# SGP30_Breakout.net
KiCad netlist of a schematic drawn in EAGLE
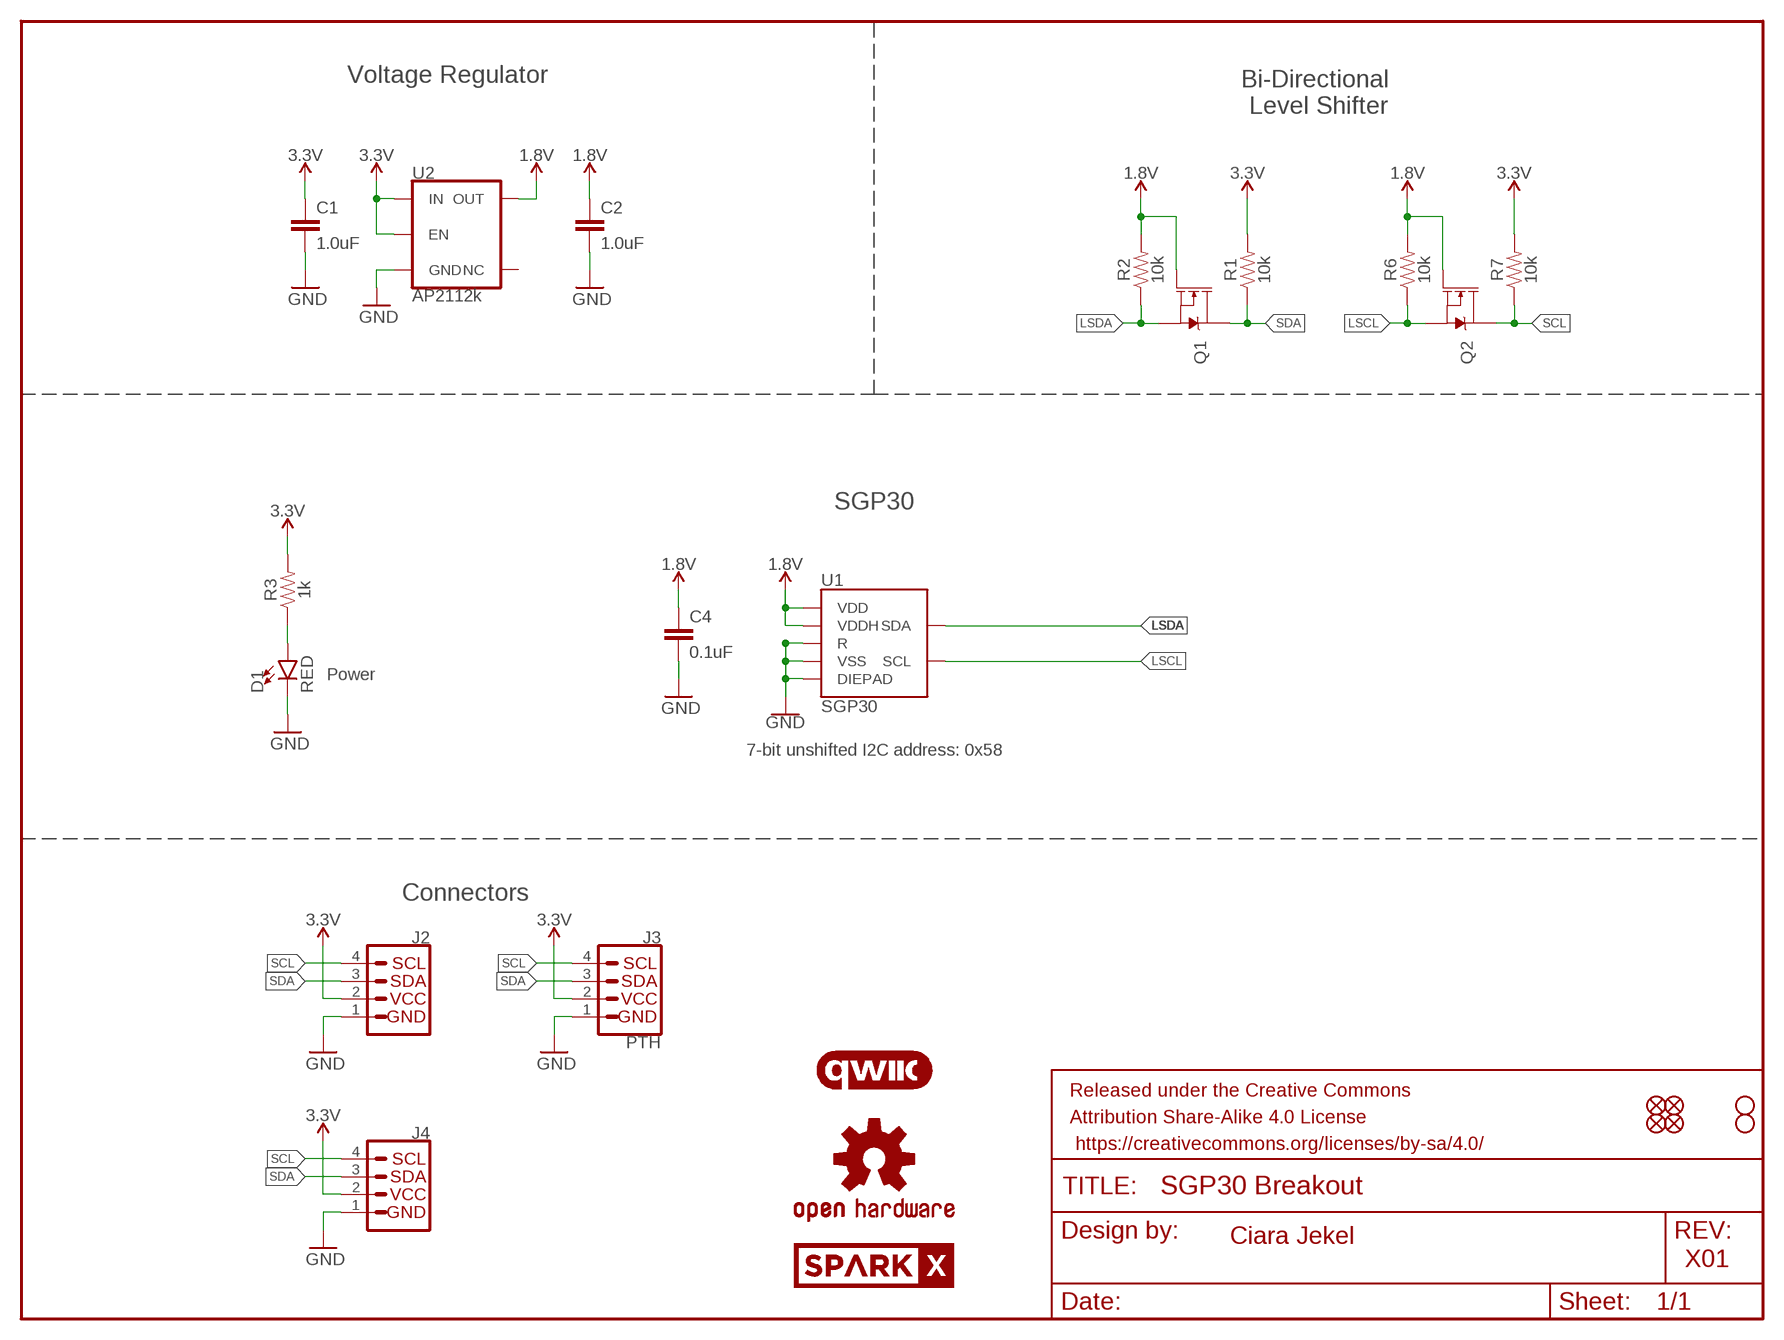
[diagram p0: schematic, sheet 1]

(export (version "E")
  (design (tool "Eeschema 10.0.6"))
  (components
    (comp (ref "C1")
      (value "1.0uF")
      (footprint "eagle-import:0603")
      (libsource (lib "eagle-import") (part "1.0UF-0603-16V-10%"))
    )
    (comp (ref "C2")
      (value "1.0uF")
      (footprint "eagle-import:0603")
      (libsource (lib "eagle-import") (part "1.0UF-0603-16V-10%"))
    )
    (comp (ref "C4")
      (value "0.1uF")
      (footprint "eagle-import:0603")
      (libsource (lib "eagle-import") (part "0.1UF-0603-25V-(+80/-20%)"))
    )
    (comp (ref "D1")
      (value "RED")
      (footprint "eagle-import:LED-0603")
      (libsource (lib "eagle-import") (part "LED-RED0603"))
    )
    (comp (ref "FRAME1")
      (value "FRAME-LETTER")
      (footprint "eagle-import:CREATIVE_COMMONS")
      (libsource (lib "eagle-import") (part "FRAME-LETTER"))
    )
    (comp (ref "J2")
      (value "QWIIC_CONNECTORJS-1MM")
      (footprint "eagle-import:1X04_1MM_RA")
      (libsource (lib "eagle-import") (part "QWIIC_CONNECTORJS-1MM"))
    )
    (comp (ref "J3")
      (value "PTH")
      (footprint "eagle-import:1X04_NO_SILK")
      (libsource (lib "eagle-import") (part "I2C_STANDARD_NO_SILK"))
    )
    (comp (ref "J4")
      (value "QWIIC_CONNECTORJS-1MM")
      (footprint "eagle-import:1X04_1MM_RA")
      (libsource (lib "eagle-import") (part "QWIIC_CONNECTORJS-1MM"))
    )
    (comp (ref "JP1")
      (value "FIDUCIALUFIDUCIAL")
      (footprint "eagle-import:MICRO-FIDUCIAL")
      (libsource (lib "eagle-import") (part "FIDUCIALUFIDUCIAL"))
    )
    (comp (ref "JP2")
      (value "FIDUCIALUFIDUCIAL")
      (footprint "eagle-import:MICRO-FIDUCIAL")
      (libsource (lib "eagle-import") (part "FIDUCIALUFIDUCIAL"))
    )
    (comp (ref "JP3")
      (value "STAND-OFF")
      (footprint "eagle-import:STAND-OFF")
      (libsource (lib "eagle-import") (part "STAND-OFF"))
    )
    (comp (ref "JP4")
      (value "STAND-OFF")
      (footprint "eagle-import:STAND-OFF")
      (libsource (lib "eagle-import") (part "STAND-OFF"))
    )
    (comp (ref "JP5")
      (value "FIDUCIALUFIDUCIAL")
      (footprint "eagle-import:MICRO-FIDUCIAL")
      (libsource (lib "eagle-import") (part "FIDUCIALUFIDUCIAL"))
    )
    (comp (ref "JP6")
      (value "FIDUCIALUFIDUCIAL")
      (footprint "eagle-import:MICRO-FIDUCIAL")
      (libsource (lib "eagle-import") (part "FIDUCIALUFIDUCIAL"))
    )
    (comp (ref "LOGO1")
      (value "OSHW-LOGOMINI")
      (footprint "eagle-import:OSHW-LOGO-MINI")
      (libsource (lib "eagle-import") (part "OSHW-LOGOMINI"))
    )
    (comp (ref "Q1")
      (value "MOSFET-NCH-BSS138")
      (footprint "eagle-import:SOT23-3")
      (libsource (lib "eagle-import") (part "MOSFET-NCH-BSS138"))
    )
    (comp (ref "Q2")
      (value "MOSFET-NCH-BSS138")
      (footprint "eagle-import:SOT23-3")
      (libsource (lib "eagle-import") (part "MOSFET-NCH-BSS138"))
    )
    (comp (ref "R1")
      (value "10k")
      (footprint "eagle-import:0603")
      (libsource (lib "eagle-import") (part "10KOHM-0603-1/10W-1%"))
    )
    (comp (ref "R2")
      (value "10k")
      (footprint "eagle-import:0603")
      (libsource (lib "eagle-import") (part "10KOHM-0603-1/10W-1%"))
    )
    (comp (ref "R3")
      (value "1k")
      (footprint "eagle-import:0603")
      (libsource (lib "eagle-import") (part "1KOHM-0603-1/10W-1%"))
    )
    (comp (ref "R6")
      (value "10k")
      (footprint "eagle-import:0603")
      (libsource (lib "eagle-import") (part "10KOHM-0603-1/10W-1%"))
    )
    (comp (ref "R7")
      (value "10k")
      (footprint "eagle-import:0603")
      (libsource (lib "eagle-import") (part "10KOHM-0603-1/10W-1%"))
    )
    (comp (ref "U$1")
      (value "SPARKX-LOGO4")
      (footprint "eagle-import:SPARKX-MEDIUM")
      (libsource (lib "eagle-import") (part "SPARKX-LOGO4"))
    )
    (comp (ref "U$2")
      (value "SPARKX-LOGO4")
      (footprint "eagle-import:SPARKX-MEDIUM")
      (libsource (lib "eagle-import") (part "SPARKX-LOGO4"))
    )
    (comp (ref "U$9")
      (value "QWIIC_LOGO_7MM")
      (footprint "eagle-import:QWIIC_7MM")
      (libsource (lib "eagle-import") (part "QWIIC_LOGO_7MM"))
    )
    (comp (ref "U1")
      (value "SGP30")
      (footprint "eagle-import:SGP30")
      (libsource (lib "eagle-import") (part "SGP30"))
    )
    (comp (ref "U2")
      (value "AP2112k")
      (footprint "eagle-import:SOT23-5")
      (libsource (lib "eagle-import") (part "MIC5504"))
    )
  )
  (nets
    (net (code "1") (name "1.8V") (class "Default")
      (node (ref "C2") (pin "1") (pinfunction "1_1") (pintype "passive"))
      (node (ref "C4") (pin "1") (pinfunction "1_1") (pintype "passive"))
      (node (ref "Q1") (pin "1") (pinfunction "G_1") (pintype "bidirectional"))
      (node (ref "Q2") (pin "1") (pinfunction "G_1") (pintype "bidirectional"))
      (node (ref "R2") (pin "2") (pinfunction "2_2") (pintype "passive"))
      (node (ref "R6") (pin "2") (pinfunction "2_2") (pintype "passive"))
      (node (ref "U1") (pin "1") (pinfunction "VDD_1") (pintype "bidirectional"))
      (node (ref "U1") (pin "5") (pinfunction "VDDH_5") (pintype "bidirectional"))
      (node (ref "U2") (pin "5") (pinfunction "OUT_5") (pintype "passive"))
    )
    (net (code "2") (name "3.3V") (class "Default")
      (node (ref "C1") (pin "1") (pinfunction "1_1") (pintype "passive"))
      (node (ref "J2") (pin "2") (pinfunction "2_2") (pintype "power_in"))
      (node (ref "J3") (pin "2") (pinfunction "VCC_2") (pintype "power_in"))
      (node (ref "J4") (pin "2") (pinfunction "2_2") (pintype "power_in"))
      (node (ref "R1") (pin "2") (pinfunction "2_2") (pintype "passive"))
      (node (ref "R3") (pin "2") (pinfunction "2_2") (pintype "passive"))
      (node (ref "R7") (pin "2") (pinfunction "2_2") (pintype "passive"))
      (node (ref "U2") (pin "1") (pinfunction "IN_1") (pintype "input"))
      (node (ref "U2") (pin "3") (pinfunction "EN_3") (pintype "input"))
    )
    (net (code "3") (name "GND") (class "Default")
      (node (ref "C1") (pin "2") (pinfunction "2_2") (pintype "passive"))
      (node (ref "C2") (pin "2") (pinfunction "2_2") (pintype "passive"))
      (node (ref "C4") (pin "2") (pinfunction "2_2") (pintype "passive"))
      (node (ref "D1") (pin "C") (pinfunction "C_C") (pintype "passive"))
      (node (ref "J2") (pin "1") (pinfunction "1_1") (pintype "power_in"))
      (node (ref "J3") (pin "1") (pinfunction "GND_1") (pintype "power_in"))
      (node (ref "J4") (pin "1") (pinfunction "1_1") (pintype "power_in"))
      (node (ref "U1") (pin "2") (pinfunction "VSS_2") (pintype "bidirectional"))
      (node (ref "U1") (pin "4") (pinfunction "R_4") (pintype "bidirectional"))
      (node (ref "U1") (pin "DIEPAD") (pinfunction "DIEPAD_DIEPAD") (pintype "bidirectional"))
      (node (ref "U2") (pin "2") (pinfunction "GND_2") (pintype "input"))
    )
    (net (code "4") (name "LSCL") (class "Default")
      (node (ref "Q2") (pin "2") (pinfunction "S_2") (pintype "bidirectional"))
      (node (ref "R6") (pin "1") (pinfunction "1_1") (pintype "passive"))
      (node (ref "U1") (pin "6") (pinfunction "SCL_6") (pintype "bidirectional"))
    )
    (net (code "5") (name "LSDA") (class "Default")
      (node (ref "Q1") (pin "2") (pinfunction "S_2") (pintype "bidirectional"))
      (node (ref "R2") (pin "1") (pinfunction "1_1") (pintype "passive"))
      (node (ref "U1") (pin "3") (pinfunction "SDA_3") (pintype "bidirectional"))
    )
    (net (code "6") (name "Net-(D1-PadA)") (class "Default")
      (node (ref "D1") (pin "A") (pinfunction "A_A") (pintype "passive"))
      (node (ref "R3") (pin "1") (pinfunction "1_1") (pintype "passive"))
    )
    (net (code "7") (name "SCL") (class "Default")
      (node (ref "J2") (pin "4") (pinfunction "4_4") (pintype "passive"))
      (node (ref "J3") (pin "4") (pinfunction "SCL_4") (pintype "passive"))
      (node (ref "J4") (pin "4") (pinfunction "4_4") (pintype "passive"))
      (node (ref "Q2") (pin "3") (pinfunction "D_3") (pintype "bidirectional"))
      (node (ref "R7") (pin "1") (pinfunction "1_1") (pintype "passive"))
    )
    (net (code "8") (name "SDA") (class "Default")
      (node (ref "J2") (pin "3") (pinfunction "3_3") (pintype "passive"))
      (node (ref "J3") (pin "3") (pinfunction "SDA_3") (pintype "passive"))
      (node (ref "J4") (pin "3") (pinfunction "3_3") (pintype "passive"))
      (node (ref "Q1") (pin "3") (pinfunction "D_3") (pintype "bidirectional"))
      (node (ref "R1") (pin "1") (pinfunction "1_1") (pintype "passive"))
    )
    (net (code "9") (name "unconnected-(U2-NC-Pad4)") (class "Default")
      (node (ref "U2") (pin "4") (pinfunction "NC_4") (pintype "no_connect"))
    )
  )
)
